# pk2socket.net
KiCad netlist of a schematic drawn in Altium Designer
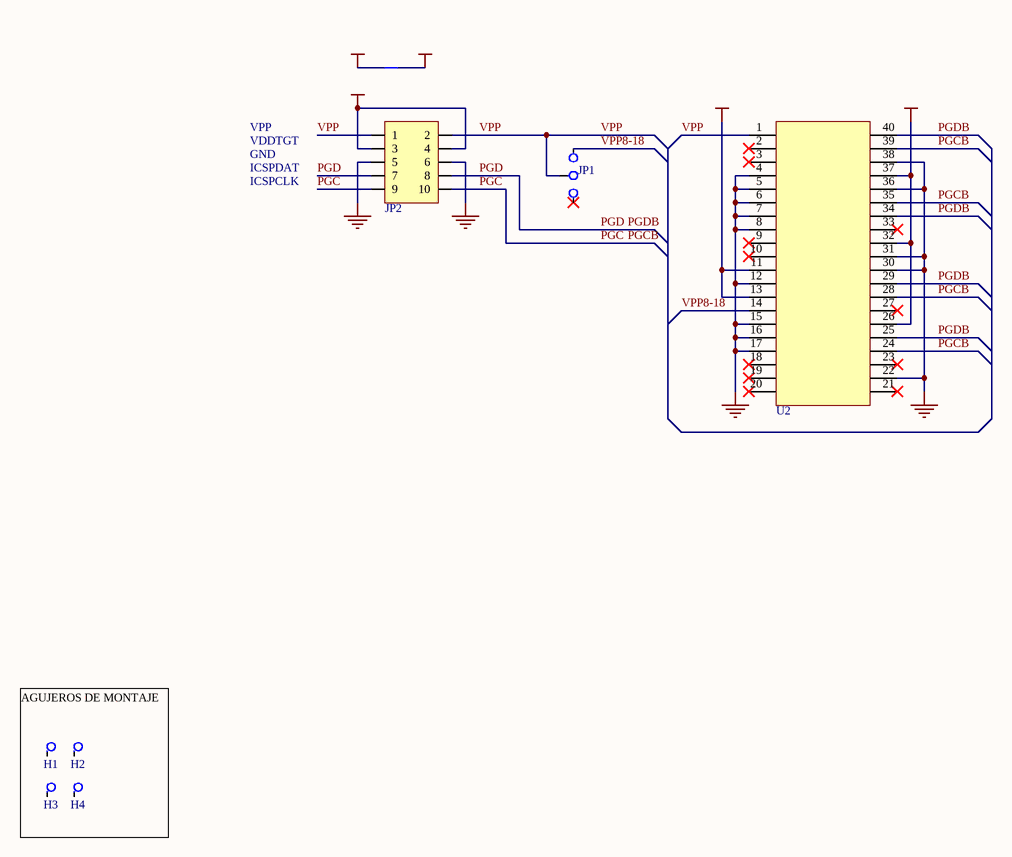
[diagram p0: pk2socket.SchDoc]

(export (version "E")
  (design (tool "Eeschema 10.0.6"))
  (components
    (comp (ref "H1")
      (value "Agujero de montaje")
      (footprint "agujero")
      (libsource (lib "FEDE") (part "Agujero de montaje"))
    )
    (comp (ref "H2")
      (value "Agujero de montaje")
      (footprint "agujero")
      (libsource (lib "FEDE") (part "Agujero de montaje"))
    )
    (comp (ref "H3")
      (value "Agujero de montaje")
      (footprint "agujero")
      (libsource (lib "FEDE") (part "Agujero de montaje"))
    )
    (comp (ref "H4")
      (value "Agujero de montaje")
      (footprint "agujero")
      (libsource (lib "FEDE") (part "Agujero de montaje"))
    )
    (comp (ref "JP1")
      (value "JP2")
      (footprint "hdr3x1")
      (description "Jumper 3 contactos")
      (libsource (lib "FEDE") (part "JP2"))
    )
    (comp (ref "JP2")
      (value "Header5x1")
      (footprint "IDC5x2")
      (description "Header 5x2")
      (libsource (lib "FEDE") (part "Header5x2"))
    )
    (comp (ref "U2")
      (value "SOCKET DIP40")
      (footprint "zif40")
      (description "Socket dip40")
      (libsource (lib "FEDE") (part "SOCKET DIP40"))
    )
    (comp (ref "W9")
      (value "CABLE")
      (footprint "1206NP")
      (description "Cable")
      (libsource (lib "FEDE") (part "CABLE"))
    )
  )
  (nets
    (net (code "1") (name "/PGC") (class "Default")
      (node (ref "JP2") (pin "10") (pinfunction "10_10") (pintype "passive"))
      (node (ref "JP2") (pin "9") (pinfunction "9_9") (pintype "passive"))
      (node (ref "U2") (pin "24") (pinfunction "24_24") (pintype "passive"))
      (node (ref "U2") (pin "28") (pinfunction "28_28") (pintype "passive"))
      (node (ref "U2") (pin "35") (pinfunction "35_35") (pintype "passive"))
      (node (ref "U2") (pin "39") (pinfunction "39_39") (pintype "passive"))
    )
    (net (code "2") (name "/PGD") (class "Default")
      (node (ref "JP2") (pin "7") (pinfunction "7_7") (pintype "passive"))
      (node (ref "JP2") (pin "8") (pinfunction "8_8") (pintype "passive"))
      (node (ref "U2") (pin "25") (pinfunction "25_25") (pintype "passive"))
      (node (ref "U2") (pin "29") (pinfunction "29_29") (pintype "passive"))
      (node (ref "U2") (pin "34") (pinfunction "34_34") (pintype "passive"))
      (node (ref "U2") (pin "40") (pinfunction "40_40") (pintype "passive"))
    )
    (net (code "3") (name "/VPP") (class "Default")
      (node (ref "JP1") (pin "2") (pinfunction "2_2") (pintype "passive"))
      (node (ref "JP2") (pin "1") (pinfunction "1_1") (pintype "passive"))
      (node (ref "JP2") (pin "2") (pinfunction "2_2") (pintype "passive"))
      (node (ref "U2") (pin "1") (pinfunction "1_1") (pintype "passive"))
    )
    (net (code "4") (name "/VPP8-18") (class "Default")
      (node (ref "JP1") (pin "3") (pinfunction "3_3") (pintype "passive"))
      (node (ref "U2") (pin "14") (pinfunction "14_14") (pintype "passive"))
    )
    (net (code "5") (name "GND") (class "Default")
      (node (ref "JP2") (pin "5") (pinfunction "5_5") (pintype "passive"))
      (node (ref "JP2") (pin "6") (pinfunction "6_6") (pintype "passive"))
      (node (ref "U2") (pin "12") (pinfunction "12_12") (pintype "passive"))
      (node (ref "U2") (pin "15") (pinfunction "15_15") (pintype "passive"))
      (node (ref "U2") (pin "16") (pinfunction "16_16") (pintype "passive"))
      (node (ref "U2") (pin "17") (pinfunction "17_17") (pintype "passive"))
      (node (ref "U2") (pin "22") (pinfunction "22_22") (pintype "passive"))
      (node (ref "U2") (pin "30") (pinfunction "30_30") (pintype "passive"))
      (node (ref "U2") (pin "31") (pinfunction "31_31") (pintype "passive"))
      (node (ref "U2") (pin "36") (pinfunction "36_36") (pintype "passive"))
      (node (ref "U2") (pin "38") (pinfunction "38_38") (pintype "passive"))
      (node (ref "U2") (pin "4") (pinfunction "4_4") (pintype "passive"))
      (node (ref "U2") (pin "5") (pinfunction "5_5") (pintype "passive"))
      (node (ref "U2") (pin "6") (pinfunction "6_6") (pintype "passive"))
      (node (ref "U2") (pin "7") (pinfunction "7_7") (pintype "passive"))
      (node (ref "U2") (pin "8") (pinfunction "8_8") (pintype "passive"))
    )
    (net (code "6") (name "VDDTGT") (class "Default")
      (node (ref "JP2") (pin "3") (pinfunction "3_3") (pintype "passive"))
      (node (ref "JP2") (pin "4") (pinfunction "4_4") (pintype "passive"))
      (node (ref "U2") (pin "11") (pinfunction "11_11") (pintype "passive"))
      (node (ref "U2") (pin "13") (pinfunction "13_13") (pintype "passive"))
      (node (ref "W9") (pin "1") (pinfunction "1_1") (pintype "passive"))
    )
    (net (code "7") (name "VDDTGT2") (class "Default")
      (node (ref "U2") (pin "26") (pinfunction "26_26") (pintype "passive"))
      (node (ref "U2") (pin "32") (pinfunction "32_32") (pintype "passive"))
      (node (ref "U2") (pin "37") (pinfunction "37_37") (pintype "passive"))
      (node (ref "W9") (pin "2") (pinfunction "2_2") (pintype "passive"))
    )
    (net (code "8") (name "unconnected-(H1-Pad1)") (class "Default")
      (node (ref "H1") (pin "1") (pinfunction "1_1") (pintype "passive"))
    )
    (net (code "9") (name "unconnected-(H2-Pad1)") (class "Default")
      (node (ref "H2") (pin "1") (pinfunction "1_1") (pintype "passive"))
    )
    (net (code "10") (name "unconnected-(H3-Pad1)") (class "Default")
      (node (ref "H3") (pin "1") (pinfunction "1_1") (pintype "passive"))
    )
    (net (code "11") (name "unconnected-(H4-Pad1)") (class "Default")
      (node (ref "H4") (pin "1") (pinfunction "1_1") (pintype "passive"))
    )
    (net (code "12") (name "unconnected-(JP1-Pad1)") (class "Default")
      (node (ref "JP1") (pin "1") (pinfunction "1_1") (pintype "passive+no_connect"))
    )
    (net (code "13") (name "unconnected-(U2-Pad2)") (class "Default")
      (node (ref "U2") (pin "2") (pinfunction "2_2") (pintype "passive+no_connect"))
    )
    (net (code "14") (name "unconnected-(U2-Pad3)") (class "Default")
      (node (ref "U2") (pin "3") (pinfunction "3_3") (pintype "passive+no_connect"))
    )
    (net (code "15") (name "unconnected-(U2-Pad9)") (class "Default")
      (node (ref "U2") (pin "9") (pinfunction "9_9") (pintype "passive+no_connect"))
    )
    (net (code "16") (name "unconnected-(U2-Pad10)") (class "Default")
      (node (ref "U2") (pin "10") (pinfunction "10_10") (pintype "passive+no_connect"))
    )
    (net (code "17") (name "unconnected-(U2-Pad18)") (class "Default")
      (node (ref "U2") (pin "18") (pinfunction "18_18") (pintype "passive+no_connect"))
    )
    (net (code "18") (name "unconnected-(U2-Pad19)") (class "Default")
      (node (ref "U2") (pin "19") (pinfunction "19_19") (pintype "passive+no_connect"))
    )
    (net (code "19") (name "unconnected-(U2-Pad20)") (class "Default")
      (node (ref "U2") (pin "20") (pinfunction "20_20") (pintype "passive+no_connect"))
    )
    (net (code "20") (name "unconnected-(U2-Pad21)") (class "Default")
      (node (ref "U2") (pin "21") (pinfunction "21_21") (pintype "passive+no_connect"))
    )
    (net (code "21") (name "unconnected-(U2-Pad23)") (class "Default")
      (node (ref "U2") (pin "23") (pinfunction "23_23") (pintype "passive+no_connect"))
    )
    (net (code "22") (name "unconnected-(U2-Pad27)") (class "Default")
      (node (ref "U2") (pin "27") (pinfunction "27_27") (pintype "passive+no_connect"))
    )
    (net (code "23") (name "unconnected-(U2-Pad33)") (class "Default")
      (node (ref "U2") (pin "33") (pinfunction "33_33") (pintype "passive+no_connect"))
    )
  )
)
